# Sheet3.net
KiCad netlist of a schematic drawn in Altium Designer
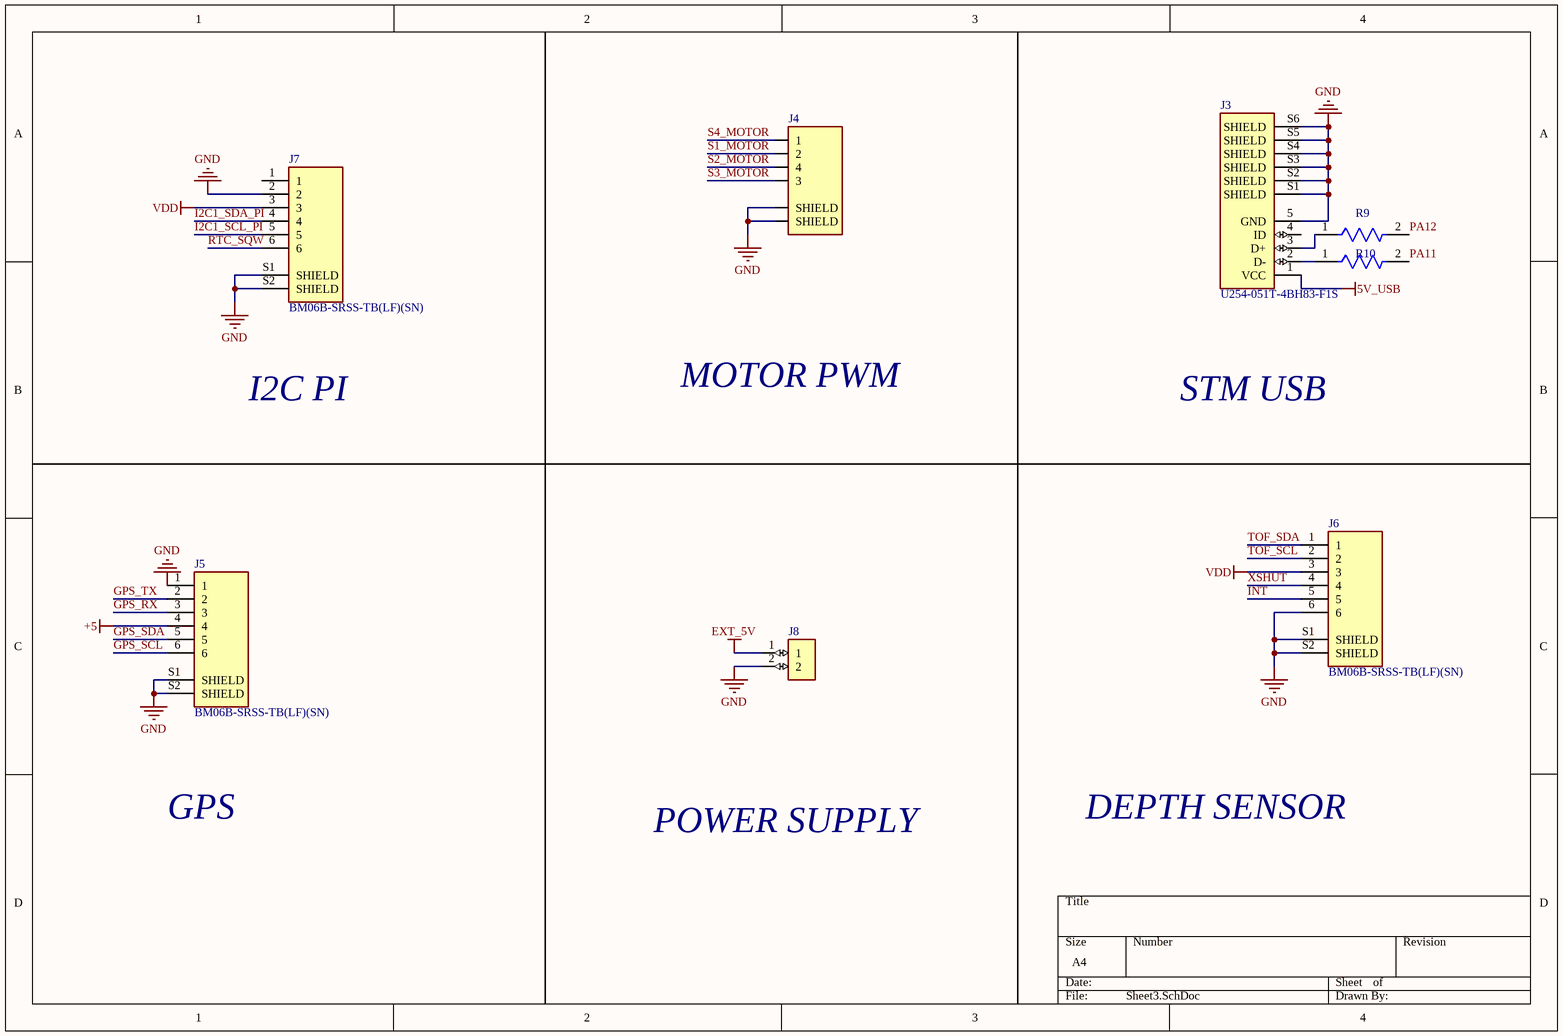
[diagram p0: Sheet3.SchDoc]

(export (version "E")
  (design (tool "Eeschema 10.0.6"))
  (components
    (comp (ref "J3")
      (value "U254-051T-4BH83-F1S")
      (footprint "XKB_U254-051T-4BH83-F1S")
      (description "USB - Micro B Female USB 2 5 SMD USB Connectors RoHS")
      (fields (field (name "MF") "XKB Industrial Precision"))
      (libsource (lib "U254-051T-4BH83-F1S") (part "U254-051T-4BH83-F1S"))
    )
    (comp (ref "J4")
      (value "SM04B-SRSS-TB(LF)(SN)")
      (footprint "JST_SM04B-SRSS-TB(LF)(SN)")
      (description "Connector Header Surface Mount, Right Angle 4 position 0.039 (1.00mm)")
      (fields (field (name "MF") "JST Sales"))
      (libsource (lib "SM04B-SRSS-TB(LF)(SN)") (part "SM04B-SRSS-TB(LF)(SN)"))
    )
    (comp (ref "J5")
      (value "BM06B-SRSS-TB(LF)(SN)")
      (footprint "JST_BM06B-SRSS-TB(LF)(SN)")
      (libsource (lib "BM06B-SRSS-TB(LF)(SN)") (part "BM06B-SRSS-TB(LF)(SN)"))
    )
    (comp (ref "J6")
      (value "BM06B-SRSS-TB(LF)(SN)")
      (footprint "JST_BM06B-SRSS-TB(LF)(SN)")
      (libsource (lib "BM06B-SRSS-TB(LF)(SN)") (part "BM06B-SRSS-TB(LF)(SN)"))
    )
    (comp (ref "J7")
      (value "BM06B-SRSS-TB(LF)(SN)")
      (footprint "JST_BM06B-SRSS-TB(LF)(SN)")
      (libsource (lib "BM06B-SRSS-TB(LF)(SN)") (part "BM06B-SRSS-TB(LF)(SN)"))
    )
    (comp (ref "J8")
      (value "SM02B-SRSS-TB(LF)(SN)")
      (footprint "SM02B-SRSS-TB(LF)(SN)")
      (description "Connector Header Surface Mount, Right Angle 2 position 0.039 (1.00mm)")
      (fields (field (name "MF") "JST Sales"))
      (libsource (lib "SM02B-SRSS-TB(LF)(SN)") (part "SM02B-SRSS-TB(LF)(SN)"))
    )
    (comp (ref "R9")
      (value "CPF0603B22RE1")
      (footprint "FP-CPF0603-MFG")
      (description "RES SMD 22Ω 0.1% 1/16W 0603")
      (fields
        (field (name "MANUFACTURER") "TE Connectivity")
        (field (name "OCTOPART") "https://octopart.com/cpf0603b22re1-te+connectivity-9539398")
      )
      (libsource (lib "Altium Content Vault") (part "1029c3af85768c4190bb7ad29bc67b5"))
    )
    (comp (ref "R10")
      (value "CPF0603B22RE1")
      (footprint "FP-CPF0603-MFG")
      (description "RES SMD 22Ω 0.1% 1/16W 0603")
      (fields
        (field (name "MANUFACTURER") "TE Connectivity")
        (field (name "OCTOPART") "https://octopart.com/cpf0603b22re1-te+connectivity-9539398")
      )
      (libsource (lib "Altium Content Vault") (part "1029c3af85768c4190bb7ad29bc67b5"))
    )
  )
  (nets
    (net (code "1") (name "+5") (class "Default")
      (node (ref "J5") (pin "4") (pinfunction "4_4") (pintype "passive"))
    )
    (net (code "2") (name "/GPS_RX") (class "Default")
      (node (ref "J5") (pin "3") (pinfunction "3_3") (pintype "passive"))
    )
    (net (code "3") (name "/GPS_SCL") (class "Default")
      (node (ref "J5") (pin "6") (pinfunction "6_6") (pintype "passive"))
    )
    (net (code "4") (name "/GPS_SDA") (class "Default")
      (node (ref "J5") (pin "5") (pinfunction "5_5") (pintype "passive"))
    )
    (net (code "5") (name "/GPS_TX") (class "Default")
      (node (ref "J5") (pin "2") (pinfunction "2_2") (pintype "passive"))
    )
    (net (code "6") (name "/I2C1_SCL_PI") (class "Default")
      (node (ref "J7") (pin "5") (pinfunction "5_5") (pintype "passive"))
    )
    (net (code "7") (name "/I2C1_SDA_PI") (class "Default")
      (node (ref "J7") (pin "4") (pinfunction "4_4") (pintype "passive"))
    )
    (net (code "8") (name "/INT") (class "Default")
      (node (ref "J6") (pin "5") (pinfunction "5_5") (pintype "passive"))
    )
    (net (code "9") (name "/PA11") (class "Default")
      (node (ref "R10") (pin "2") (pinfunction "2_2") (pintype "passive"))
    )
    (net (code "10") (name "/PA12") (class "Default")
      (node (ref "R9") (pin "2") (pinfunction "2_2") (pintype "passive"))
    )
    (net (code "11") (name "/RTC_SQW") (class "Default")
      (node (ref "J7") (pin "6") (pinfunction "6_6") (pintype "passive"))
    )
    (net (code "12") (name "/S1_MOTOR") (class "Default")
      (node (ref "J4") (pin "2") (pinfunction "2_2") (pintype "passive"))
    )
    (net (code "13") (name "/S2_MOTOR") (class "Default")
      (node (ref "J4") (pin "4") (pinfunction "4_4") (pintype "passive"))
    )
    (net (code "14") (name "/S3_MOTOR") (class "Default")
      (node (ref "J4") (pin "3") (pinfunction "3_3") (pintype "passive"))
    )
    (net (code "15") (name "/S4_MOTOR") (class "Default")
      (node (ref "J4") (pin "1") (pinfunction "1_1") (pintype "passive"))
    )
    (net (code "16") (name "/TOF_SCL") (class "Default")
      (node (ref "J6") (pin "2") (pinfunction "2_2") (pintype "passive"))
    )
    (net (code "17") (name "/TOF_SDA") (class "Default")
      (node (ref "J6") (pin "1") (pinfunction "1_1") (pintype "passive"))
    )
    (net (code "18") (name "/XSHUT") (class "Default")
      (node (ref "J6") (pin "4") (pinfunction "4_4") (pintype "passive"))
    )
    (net (code "19") (name "5V_USB") (class "Default")
      (node (ref "J3") (pin "1") (pinfunction "VCC_1") (pintype "power_in"))
    )
    (net (code "20") (name "EXT_5V") (class "Default")
      (node (ref "J8") (pin "1") (pinfunction "1_1") (pintype "bidirectional"))
    )
    (net (code "21") (name "GND") (class "Default")
      (node (ref "J3") (pin "5") (pinfunction "GND_5") (pintype "power_in"))
      (node (ref "J3") (pin "S1") (pinfunction "SHIELD_S1") (pintype "passive"))
      (node (ref "J3") (pin "S2") (pinfunction "SHIELD_S2") (pintype "passive"))
      (node (ref "J3") (pin "S3") (pinfunction "SHIELD_S3") (pintype "passive"))
      (node (ref "J3") (pin "S4") (pinfunction "SHIELD_S4") (pintype "passive"))
      (node (ref "J3") (pin "S5") (pinfunction "SHIELD_S5") (pintype "passive"))
      (node (ref "J3") (pin "S6") (pinfunction "SHIELD_S6") (pintype "passive"))
      (node (ref "J4") (pin "S1") (pinfunction "SHIELD_S1") (pintype "passive"))
      (node (ref "J4") (pin "S2") (pinfunction "SHIELD_S2") (pintype "passive"))
      (node (ref "J5") (pin "1") (pinfunction "1_1") (pintype "passive"))
      (node (ref "J5") (pin "S1") (pinfunction "SHIELD_S1") (pintype "passive"))
      (node (ref "J5") (pin "S2") (pinfunction "SHIELD_S2") (pintype "passive"))
      (node (ref "J6") (pin "6") (pinfunction "6_6") (pintype "passive"))
      (node (ref "J6") (pin "S1") (pinfunction "SHIELD_S1") (pintype "passive"))
      (node (ref "J6") (pin "S2") (pinfunction "SHIELD_S2") (pintype "passive"))
      (node (ref "J7") (pin "2") (pinfunction "2_2") (pintype "passive"))
      (node (ref "J7") (pin "S1") (pinfunction "SHIELD_S1") (pintype "passive"))
      (node (ref "J7") (pin "S2") (pinfunction "SHIELD_S2") (pintype "passive"))
      (node (ref "J8") (pin "2") (pinfunction "2_2") (pintype "bidirectional"))
    )
    (net (code "22") (name "Net-(J3-D+)") (class "Default")
      (node (ref "J3") (pin "3") (pinfunction "D+_3") (pintype "bidirectional"))
      (node (ref "R9") (pin "1") (pinfunction "1_1") (pintype "passive"))
    )
    (net (code "23") (name "Net-(J3-D-)") (class "Default")
      (node (ref "J3") (pin "2") (pinfunction "D-_2") (pintype "bidirectional"))
      (node (ref "R10") (pin "1") (pinfunction "1_1") (pintype "passive"))
    )
    (net (code "24") (name "VDD") (class "Default")
      (node (ref "J6") (pin "3") (pinfunction "3_3") (pintype "passive"))
      (node (ref "J7") (pin "3") (pinfunction "3_3") (pintype "passive"))
    )
    (net (code "25") (name "unconnected-(J3-ID-Pad4)") (class "Default")
      (node (ref "J3") (pin "4") (pinfunction "ID_4") (pintype "bidirectional"))
    )
    (net (code "26") (name "unconnected-(J7-Pad1)") (class "Default")
      (node (ref "J7") (pin "1") (pinfunction "1_1") (pintype "passive"))
    )
  )
)
